# untitled.net
KiCad netlist of a schematic drawn in EAGLE
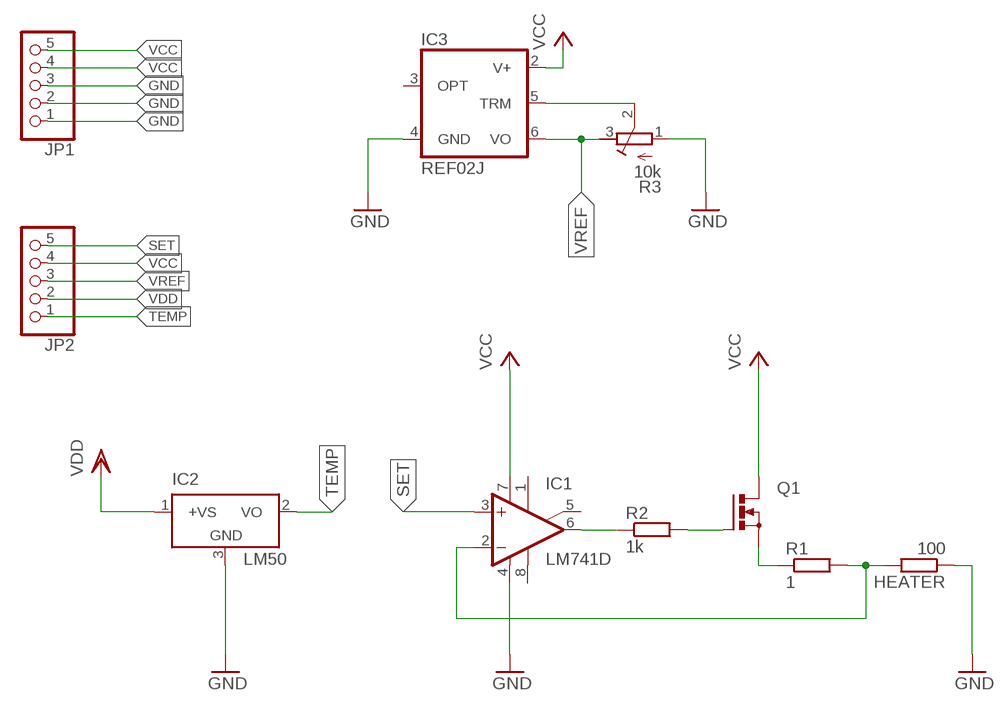
[diagram p0: schematic, sheet 1]

(export (version "E")
  (design (tool "Eeschema 10.0.6"))
  (components
    (comp (ref "HEATER")
      (value "100")
      (footprint "eagle-import:WSC0001")
      (libsource (lib "eagle-import") (part "R-EU_WSC0001"))
    )
    (comp (ref "IC1")
      (value "LM741D")
      (footprint "eagle-import:SO08")
      (libsource (lib "eagle-import") (part "741DLM"))
    )
    (comp (ref "IC2")
      (value "LM50")
      (footprint "eagle-import:SOT23")
      (libsource (lib "eagle-import") (part "LM50"))
    )
    (comp (ref "IC3")
      (value "REF02J")
      (footprint "eagle-import:TO99")
      (libsource (lib "eagle-import") (part "REF02J"))
    )
    (comp (ref "JP1")
      (value "PINHD-1X5")
      (footprint "eagle-import:1X05")
      (libsource (lib "eagle-import") (part "PINHD-1X5"))
    )
    (comp (ref "JP2")
      (value "PINHD-1X5")
      (footprint "eagle-import:1X05")
      (libsource (lib "eagle-import") (part "PINHD-1X5"))
    )
    (comp (ref "Q1")
      (value "N-MOSFET-SO8S")
      (footprint "eagle-import:SO-08")
      (libsource (lib "eagle-import") (part "N-MOSFET-SO8S"))
    )
    (comp (ref "R1")
      (value "1")
      (footprint "eagle-import:R1206")
      (libsource (lib "eagle-import") (part "R-EU_R1206"))
    )
    (comp (ref "R2")
      (value "1k")
      (footprint "eagle-import:R1206")
      (libsource (lib "eagle-import") (part "R-EU_R1206"))
    )
    (comp (ref "R3")
      (value "10k")
      (footprint "eagle-import:RTRIM3103")
      (libsource (lib "eagle-import") (part "R-TRIMM3103"))
    )
  )
  (nets
    (net (code "1") (name "GND") (class "Default")
      (node (ref "HEATER") (pin "1") (pinfunction "1_1") (pintype "passive"))
      (node (ref "IC1") (pin "4") (pinfunction "V-_4") (pintype "power_in"))
      (node (ref "IC2") (pin "3") (pinfunction "GND_3") (pintype "power_in"))
      (node (ref "IC3") (pin "4") (pinfunction "GND_4") (pintype "power_in"))
      (node (ref "JP1") (pin "1") (pinfunction "1_1") (pintype "passive"))
      (node (ref "JP1") (pin "2") (pinfunction "2_2") (pintype "passive"))
      (node (ref "JP1") (pin "3") (pinfunction "3_3") (pintype "passive"))
      (node (ref "R3") (pin "1") (pinfunction "A_1") (pintype "passive"))
    )
    (net (code "2") (name "Net-(IC1--IN)") (class "Default")
      (node (ref "HEATER") (pin "2") (pinfunction "2_2") (pintype "passive"))
      (node (ref "IC1") (pin "2") (pinfunction "-IN_2") (pintype "input"))
      (node (ref "R1") (pin "2") (pinfunction "2_2") (pintype "passive"))
    )
    (net (code "3") (name "Net-(IC1-OUT)") (class "Default")
      (node (ref "IC1") (pin "6") (pinfunction "OUT_6") (pintype "output"))
      (node (ref "R2") (pin "1") (pinfunction "1_1") (pintype "passive"))
    )
    (net (code "4") (name "Net-(IC3-TRM)") (class "Default")
      (node (ref "IC3") (pin "5") (pinfunction "TRM_5") (pintype "input"))
      (node (ref "R3") (pin "2") (pinfunction "S_2") (pintype "passive"))
    )
    (net (code "5") (name "Net-(Q1-G)") (class "Default")
      (node (ref "Q1") (pin "4") (pinfunction "G_4") (pintype "passive"))
      (node (ref "R2") (pin "2") (pinfunction "2_2") (pintype "passive"))
    )
    (net (code "6") (name "Net-(Q1-S-Pad1)") (class "Default")
      (node (ref "Q1") (pin "1") (pinfunction "S_1") (pintype "passive"))
      (node (ref "Q1") (pin "2") (pinfunction "S_2") (pintype "passive"))
      (node (ref "Q1") (pin "3") (pinfunction "S_3") (pintype "passive"))
      (node (ref "R1") (pin "1") (pinfunction "1_1") (pintype "passive"))
    )
    (net (code "7") (name "SET") (class "Default")
      (node (ref "IC1") (pin "3") (pinfunction "+IN_3") (pintype "input"))
      (node (ref "JP2") (pin "5") (pinfunction "5_5") (pintype "passive"))
    )
    (net (code "8") (name "TEMP") (class "Default")
      (node (ref "IC2") (pin "2") (pinfunction "VO_2") (pintype "input"))
      (node (ref "JP2") (pin "1") (pinfunction "1_1") (pintype "passive"))
    )
    (net (code "9") (name "VCC") (class "Default")
      (node (ref "IC1") (pin "7") (pinfunction "V+_7") (pintype "power_in"))
      (node (ref "IC3") (pin "2") (pinfunction "V+_2") (pintype "power_in"))
      (node (ref "JP1") (pin "4") (pinfunction "4_4") (pintype "passive"))
      (node (ref "JP1") (pin "5") (pinfunction "5_5") (pintype "passive"))
      (node (ref "JP2") (pin "4") (pinfunction "4_4") (pintype "passive"))
      (node (ref "Q1") (pin "5") (pinfunction "D_5") (pintype "passive"))
      (node (ref "Q1") (pin "6") (pinfunction "D_6") (pintype "passive"))
      (node (ref "Q1") (pin "7") (pinfunction "D_7") (pintype "passive"))
      (node (ref "Q1") (pin "8") (pinfunction "D_8") (pintype "passive"))
    )
    (net (code "10") (name "VDD") (class "Default")
      (node (ref "IC2") (pin "1") (pinfunction "+VS_1") (pintype "input"))
      (node (ref "JP2") (pin "2") (pinfunction "2_2") (pintype "passive"))
    )
    (net (code "11") (name "VREF") (class "Default")
      (node (ref "IC3") (pin "6") (pinfunction "VO_6") (pintype "output"))
      (node (ref "JP2") (pin "3") (pinfunction "3_3") (pintype "passive"))
      (node (ref "R3") (pin "3") (pinfunction "E_3") (pintype "passive"))
    )
    (net (code "12") (name "unconnected-(IC1-ON1-Pad1)") (class "Default")
      (node (ref "IC1") (pin "1") (pinfunction "ON1_1") (pintype "passive"))
    )
    (net (code "13") (name "unconnected-(IC1-ON2-Pad5)") (class "Default")
      (node (ref "IC1") (pin "5") (pinfunction "ON2_5") (pintype "passive"))
    )
    (net (code "14") (name "unconnected-(IC1-OPT-Pad8)") (class "Default")
      (node (ref "IC1") (pin "8") (pinfunction "OPT_8") (pintype "passive"))
    )
    (net (code "15") (name "unconnected-(IC3-OPT-Pad3)") (class "Default")
      (node (ref "IC3") (pin "3") (pinfunction "OPT_3") (pintype "output"))
    )
  )
)
